# Sheet2.net
KiCad netlist of a schematic drawn in Altium Designer
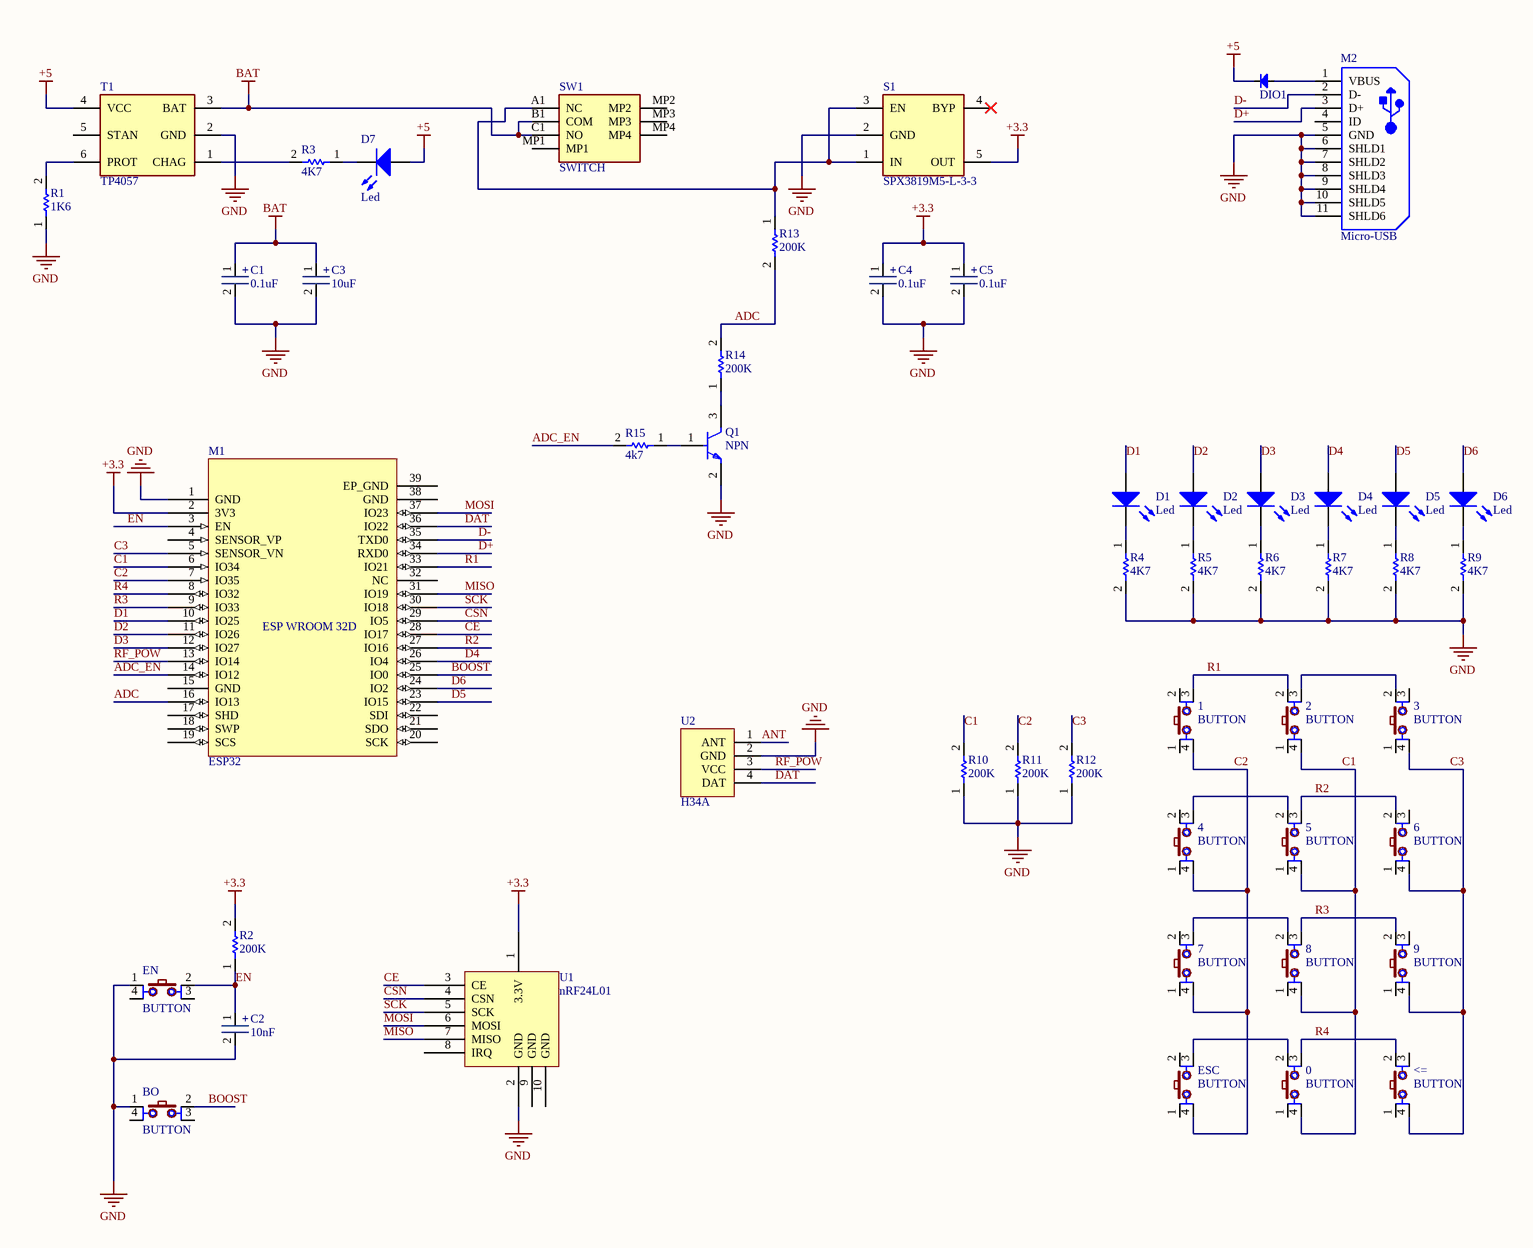
[diagram p0: Sheet2.SchDoc]

(export (version "E")
  (design (tool "Eeschema 10.0.6"))
  (components
    (comp (ref "0")
      (value "BUTTON")
      (footprint "BUTTON 4X4mm")
      (libsource (lib "Librarys") (part "BUTTON 4 PIN"))
    )
    (comp (ref "1")
      (value "BUTTON")
      (footprint "BUTTON 4X4mm")
      (libsource (lib "Librarys") (part "BUTTON 4 PIN"))
    )
    (comp (ref "2")
      (value "BUTTON")
      (footprint "BUTTON 4X4mm")
      (libsource (lib "Librarys") (part "BUTTON 4 PIN"))
    )
    (comp (ref "3")
      (value "BUTTON")
      (footprint "BUTTON 4X4mm")
      (libsource (lib "Librarys") (part "BUTTON 4 PIN"))
    )
    (comp (ref "4")
      (value "BUTTON")
      (footprint "BUTTON 4X4mm")
      (libsource (lib "Librarys") (part "BUTTON 4 PIN"))
    )
    (comp (ref "5")
      (value "BUTTON")
      (footprint "BUTTON 4X4mm")
      (libsource (lib "Librarys") (part "BUTTON 4 PIN"))
    )
    (comp (ref "6")
      (value "BUTTON")
      (footprint "BUTTON 4X4mm")
      (libsource (lib "Librarys") (part "BUTTON 4 PIN"))
    )
    (comp (ref "7")
      (value "BUTTON")
      (footprint "BUTTON 4X4mm")
      (libsource (lib "Librarys") (part "BUTTON 4 PIN"))
    )
    (comp (ref "8")
      (value "BUTTON")
      (footprint "BUTTON 4X4mm")
      (libsource (lib "Librarys") (part "BUTTON 4 PIN"))
    )
    (comp (ref "9")
      (value "BUTTON")
      (footprint "BUTTON 4X4mm")
      (libsource (lib "Librarys") (part "BUTTON 4 PIN"))
    )
    (comp (ref "<=")
      (value "BUTTON")
      (footprint "BUTTON 4X4mm")
      (libsource (lib "Librarys") (part "BUTTON 4 PIN"))
    )
    (comp (ref "BO")
      (value "BUTTON")
      (footprint "BUTTON 3x4mm 4PIN")
      (libsource (lib "Librarys") (part "BUTTON 4 PIN"))
    )
    (comp (ref "C1")
      (value "0.1uF")
      (footprint "Cap_0603_A")
      (description "General Purpose Ceramic Capacitor, 0603, 1nF, 10%, X7R, 15%, 50V")
      (fields (field (name "VOLTAGE") "50V") (field (name "TOLERANCE") "10%"))
      (libsource (lib "ResCapTransDio") (part "Capacitor"))
    )
    (comp (ref "C2")
      (value "10nF")
      (footprint "Cap_0603_A")
      (description "General Purpose Ceramic Capacitor, 0603, 1nF, 10%, X7R, 15%, 50V")
      (fields (field (name "VOLTAGE") "50V") (field (name "TOLERANCE") "10%"))
      (libsource (lib "ResCapTransDio") (part "Capacitor"))
    )
    (comp (ref "C3")
      (value "10uF")
      (footprint "Cap_0603_A")
      (description "General Purpose Ceramic Capacitor, 0603, 1nF, 10%, X7R, 15%, 50V")
      (fields (field (name "VOLTAGE") "50V") (field (name "TOLERANCE") "10%"))
      (libsource (lib "ResCapTransDio") (part "Capacitor"))
    )
    (comp (ref "C4")
      (value "0.1uF")
      (footprint "Cap_0603_A")
      (description "General Purpose Ceramic Capacitor, 0603, 1nF, 10%, X7R, 15%, 50V")
      (fields (field (name "VOLTAGE") "50V") (field (name "TOLERANCE") "10%"))
      (libsource (lib "ResCapTransDio") (part "Capacitor"))
    )
    (comp (ref "C5")
      (value "0.1uF")
      (footprint "Cap_0603_A")
      (description "General Purpose Ceramic Capacitor, 0603, 1nF, 10%, X7R, 15%, 50V")
      (fields (field (name "VOLTAGE") "50V") (field (name "TOLERANCE") "10%"))
      (libsource (lib "ResCapTransDio") (part "Capacitor"))
    )
    (comp (ref "D1") (value "Led") (footprint "LED 0603") (libsource (lib "ResCapTransDio") (part "Led")))
    (comp (ref "D2") (value "Led") (footprint "LED 0603") (libsource (lib "ResCapTransDio") (part "Led")))
    (comp (ref "D3") (value "Led") (footprint "LED 0603") (libsource (lib "ResCapTransDio") (part "Led")))
    (comp (ref "D4") (value "Led") (footprint "LED 0603") (libsource (lib "ResCapTransDio") (part "Led")))
    (comp (ref "D5") (value "Led") (footprint "LED 0603") (libsource (lib "ResCapTransDio") (part "Led")))
    (comp (ref "D6") (value "Led") (footprint "LED 0603") (libsource (lib "ResCapTransDio") (part "Led")))
    (comp (ref "D7") (value "Led") (footprint "LED 0603") (libsource (lib "ResCapTransDio") (part "Led")))
    (comp (ref "DIO1")
      (value "Diode SMD")
      (footprint "DIO-SMD-123")
      (description "Default Diode")
      (fields (field (name "PUBLISHER") "Altium Limited"))
      (libsource (lib "TechMT.VN_Lib_Project v2") (part "Diode SMD"))
    )
    (comp (ref "EN")
      (value "BUTTON")
      (footprint "BUTTON 3x4mm 4PIN")
      (libsource (lib "Librarys") (part "BUTTON 4 PIN"))
    )
    (comp (ref "ESC")
      (value "BUTTON")
      (footprint "BUTTON 4X4mm")
      (libsource (lib "Librarys") (part "BUTTON 4 PIN"))
    )
    (comp (ref "M1")
      (value "ESP32")
      (footprint "ESP32-WROOM-32D")
      (libsource (lib "ESP-WROOM-32D") (part "ESP32"))
    )
    (comp (ref "M2")
      (value "Micro-USB")
      (footprint "2.0 5 PIN SMD")
      (libsource (lib "Librarys") (part "Micro-USB"))
    )
    (comp (ref "Q1")
      (value "NPN")
      (footprint "FP-SOT23-IPC_C")
      (libsource (lib "ResCapTransDio") (part "NPN"))
    )
    (comp (ref "R1")
      (value "1K6")
      (footprint "Res_0603")
      (libsource (lib "ResCapTransDio") (part "Resistor"))
    )
    (comp (ref "R2")
      (value "200K")
      (footprint "Res_0603")
      (libsource (lib "ResCapTransDio") (part "Resistor"))
    )
    (comp (ref "R3")
      (value "4K7")
      (footprint "Res_0603")
      (libsource (lib "ResCapTransDio") (part "Resistor"))
    )
    (comp (ref "R4")
      (value "4K7")
      (footprint "Res_0603")
      (libsource (lib "ResCapTransDio") (part "Resistor"))
    )
    (comp (ref "R5")
      (value "4K7")
      (footprint "Res_0603")
      (libsource (lib "ResCapTransDio") (part "Resistor"))
    )
    (comp (ref "R6")
      (value "4K7")
      (footprint "Res_0603")
      (libsource (lib "ResCapTransDio") (part "Resistor"))
    )
    (comp (ref "R7")
      (value "4K7")
      (footprint "Res_0603")
      (libsource (lib "ResCapTransDio") (part "Resistor"))
    )
    (comp (ref "R8")
      (value "4K7")
      (footprint "Res_0603")
      (libsource (lib "ResCapTransDio") (part "Resistor"))
    )
    (comp (ref "R9")
      (value "4K7")
      (footprint "Res_0603")
      (libsource (lib "ResCapTransDio") (part "Resistor"))
    )
    (comp (ref "R10")
      (value "200K")
      (footprint "Res_0603")
      (libsource (lib "ResCapTransDio") (part "Resistor"))
    )
    (comp (ref "R11")
      (value "200K")
      (footprint "Res_0603")
      (libsource (lib "ResCapTransDio") (part "Resistor"))
    )
    (comp (ref "R12")
      (value "200K")
      (footprint "Res_0603")
      (libsource (lib "ResCapTransDio") (part "Resistor"))
    )
    (comp (ref "R13")
      (value "200K")
      (footprint "Res_0603")
      (libsource (lib "ResCapTransDio") (part "Resistor"))
    )
    (comp (ref "R14")
      (value "200K")
      (footprint "Res_0603")
      (libsource (lib "ResCapTransDio") (part "Resistor"))
    )
    (comp (ref "R15")
      (value "4k7")
      (footprint "Res_0603")
      (libsource (lib "ResCapTransDio") (part "Resistor"))
    )
    (comp (ref "S1")
      (value "SPX3819M5-L-3-3")
      (footprint "FP-C04-091-OT-IPC_A")
      (description "Regulator 250mA")
      (libsource (lib "Regulator") (part "SPX3819M5-L-3-3"))
    )
    (comp (ref "SW1") (value "SWITCH") (footprint "MSK12C02") (libsource (lib "Librarys") (part "SWITCH")))
    (comp (ref "T1") (value "TP4057") (footprint "TP4057") (libsource (lib "Librarys") (part "TP4057")))
    (comp (ref "U1")
      (value "nRF24L01")
      (footprint "NRF24L01 + PA SMD")
      (libsource (lib "MODULEs") (part "nRF24L01"))
    )
    (comp (ref "U2") (value "H34A") (footprint "H34A") (libsource (lib "MODULEs") (part "H34A")))
  )
  (nets
    (net (code "1") (name "+3.3") (class "Default")
      (node (ref "C4") (pin "1") (pinfunction "1_1") (pintype "passive"))
      (node (ref "C5") (pin "1") (pinfunction "1_1") (pintype "passive"))
      (node (ref "M1") (pin "2") (pinfunction "3V3_2") (pintype "passive"))
      (node (ref "R2") (pin "2") (pinfunction "2_2") (pintype "passive"))
      (node (ref "S1") (pin "5") (pinfunction "OUT_5") (pintype "passive"))
      (node (ref "U1") (pin "1") (pinfunction "3.3V_1") (pintype "passive"))
    )
    (net (code "2") (name "+5") (class "Default")
      (node (ref "D7") (pin "1") (pinfunction "A_1") (pintype "passive"))
      (node (ref "DIO1") (pin "2") (pinfunction "K_2") (pintype "passive"))
      (node (ref "T1") (pin "4") (pinfunction "VCC_4") (pintype "power_in"))
    )
    (net (code "3") (name "/ADC") (class "Default")
      (node (ref "M1") (pin "16") (pinfunction "IO13_16") (pintype "bidirectional"))
      (node (ref "R13") (pin "2") (pinfunction "2_2") (pintype "passive"))
      (node (ref "R14") (pin "2") (pinfunction "2_2") (pintype "passive"))
    )
    (net (code "4") (name "/ADC_EN") (class "Default")
      (node (ref "M1") (pin "14") (pinfunction "IO12_14") (pintype "bidirectional"))
      (node (ref "R15") (pin "2") (pinfunction "2_2") (pintype "passive"))
    )
    (net (code "5") (name "/ANT") (class "Default")
      (node (ref "U2") (pin "1") (pinfunction "ANT_1") (pintype "passive"))
    )
    (net (code "6") (name "/BOOST") (class "Default")
      (node (ref "BO") (pin "2") (pinfunction "2_2") (pintype "passive"))
      (node (ref "M1") (pin "25") (pinfunction "IO0_25") (pintype "bidirectional"))
    )
    (net (code "7") (name "/C1") (class "Default")
      (node (ref "0") (pin "4") (pinfunction "4_4") (pintype "passive"))
      (node (ref "2") (pin "4") (pinfunction "4_4") (pintype "passive"))
      (node (ref "5") (pin "4") (pinfunction "4_4") (pintype "passive"))
      (node (ref "8") (pin "4") (pinfunction "4_4") (pintype "passive"))
      (node (ref "M1") (pin "6") (pinfunction "IO34_6") (pintype "input"))
      (node (ref "R10") (pin "2") (pinfunction "2_2") (pintype "passive"))
    )
    (net (code "8") (name "/C2") (class "Default")
      (node (ref "1") (pin "4") (pinfunction "4_4") (pintype "passive"))
      (node (ref "4") (pin "4") (pinfunction "4_4") (pintype "passive"))
      (node (ref "7") (pin "4") (pinfunction "4_4") (pintype "passive"))
      (node (ref "ESC") (pin "4") (pinfunction "4_4") (pintype "passive"))
      (node (ref "M1") (pin "7") (pinfunction "IO35_7") (pintype "input"))
      (node (ref "R11") (pin "2") (pinfunction "2_2") (pintype "passive"))
    )
    (net (code "9") (name "/C3") (class "Default")
      (node (ref "3") (pin "4") (pinfunction "4_4") (pintype "passive"))
      (node (ref "6") (pin "4") (pinfunction "4_4") (pintype "passive"))
      (node (ref "9") (pin "4") (pinfunction "4_4") (pintype "passive"))
      (node (ref "<=") (pin "4") (pinfunction "4_4") (pintype "passive"))
      (node (ref "M1") (pin "5") (pinfunction "SENSOR_VN_5") (pintype "input"))
      (node (ref "R12") (pin "2") (pinfunction "2_2") (pintype "passive"))
    )
    (net (code "10") (name "/CE") (class "Default")
      (node (ref "M1") (pin "28") (pinfunction "IO17_28") (pintype "bidirectional"))
      (node (ref "U1") (pin "3") (pinfunction "CE_3") (pintype "passive"))
    )
    (net (code "11") (name "/CSN") (class "Default")
      (node (ref "M1") (pin "29") (pinfunction "IO5_29") (pintype "bidirectional"))
      (node (ref "U1") (pin "4") (pinfunction "CSN_4") (pintype "passive"))
    )
    (net (code "12") (name "/D+") (class "Default")
      (node (ref "M1") (pin "34") (pinfunction "RXD0_34") (pintype "bidirectional"))
      (node (ref "M2") (pin "3") (pinfunction "D+_3") (pintype "passive"))
    )
    (net (code "13") (name "/D-") (class "Default")
      (node (ref "M1") (pin "35") (pinfunction "TXD0_35") (pintype "bidirectional"))
      (node (ref "M2") (pin "2") (pinfunction "D-_2") (pintype "passive"))
    )
    (net (code "14") (name "/D1") (class "Default")
      (node (ref "D1") (pin "1") (pinfunction "A_1") (pintype "passive"))
      (node (ref "M1") (pin "10") (pinfunction "IO25_10") (pintype "bidirectional"))
    )
    (net (code "15") (name "/D2") (class "Default")
      (node (ref "D2") (pin "1") (pinfunction "A_1") (pintype "passive"))
      (node (ref "M1") (pin "11") (pinfunction "IO26_11") (pintype "bidirectional"))
    )
    (net (code "16") (name "/D3") (class "Default")
      (node (ref "D3") (pin "1") (pinfunction "A_1") (pintype "passive"))
      (node (ref "M1") (pin "12") (pinfunction "IO27_12") (pintype "bidirectional"))
    )
    (net (code "17") (name "/D4") (class "Default")
      (node (ref "D4") (pin "1") (pinfunction "A_1") (pintype "passive"))
      (node (ref "M1") (pin "26") (pinfunction "IO4_26") (pintype "bidirectional"))
    )
    (net (code "18") (name "/D5") (class "Default")
      (node (ref "D5") (pin "1") (pinfunction "A_1") (pintype "passive"))
      (node (ref "M1") (pin "23") (pinfunction "IO15_23") (pintype "bidirectional"))
    )
    (net (code "19") (name "/D6") (class "Default")
      (node (ref "D6") (pin "1") (pinfunction "A_1") (pintype "passive"))
      (node (ref "M1") (pin "24") (pinfunction "IO2_24") (pintype "bidirectional"))
    )
    (net (code "20") (name "/DAT") (class "Default")
      (node (ref "M1") (pin "36") (pinfunction "IO22_36") (pintype "bidirectional"))
      (node (ref "U2") (pin "4") (pinfunction "DAT_4") (pintype "passive"))
    )
    (net (code "21") (name "/EN") (class "Default")
      (node (ref "C2") (pin "1") (pinfunction "1_1") (pintype "passive"))
      (node (ref "EN") (pin "2") (pinfunction "2_2") (pintype "passive"))
      (node (ref "M1") (pin "3") (pinfunction "EN_3") (pintype "input"))
      (node (ref "R2") (pin "1") (pinfunction "1_1") (pintype "passive"))
    )
    (net (code "22") (name "/MISO") (class "Default")
      (node (ref "M1") (pin "31") (pinfunction "IO19_31") (pintype "bidirectional"))
      (node (ref "U1") (pin "7") (pinfunction "MISO_7") (pintype "passive"))
    )
    (net (code "23") (name "/MOSI") (class "Default")
      (node (ref "M1") (pin "37") (pinfunction "IO23_37") (pintype "bidirectional"))
      (node (ref "U1") (pin "6") (pinfunction "MOSI_6") (pintype "passive"))
    )
    (net (code "24") (name "/R1") (class "Default")
      (node (ref "1") (pin "3") (pinfunction "3_3") (pintype "passive"))
      (node (ref "2") (pin "2") (pinfunction "2_2") (pintype "passive"))
      (node (ref "M1") (pin "33") (pinfunction "IO21_33") (pintype "bidirectional"))
    )
    (net (code "25") (name "/R2") (class "Default")
      (node (ref "5") (pin "3") (pinfunction "3_3") (pintype "passive"))
      (node (ref "6") (pin "2") (pinfunction "2_2") (pintype "passive"))
      (node (ref "M1") (pin "27") (pinfunction "IO16_27") (pintype "bidirectional"))
    )
    (net (code "26") (name "/R3") (class "Default")
      (node (ref "8") (pin "3") (pinfunction "3_3") (pintype "passive"))
      (node (ref "9") (pin "2") (pinfunction "2_2") (pintype "passive"))
      (node (ref "M1") (pin "9") (pinfunction "IO33_9") (pintype "bidirectional"))
    )
    (net (code "27") (name "/R4") (class "Default")
      (node (ref "0") (pin "3") (pinfunction "3_3") (pintype "passive"))
      (node (ref "<=") (pin "2") (pinfunction "2_2") (pintype "passive"))
      (node (ref "M1") (pin "8") (pinfunction "IO32_8") (pintype "bidirectional"))
    )
    (net (code "28") (name "/RF_POW") (class "Default")
      (node (ref "M1") (pin "13") (pinfunction "IO14_13") (pintype "bidirectional"))
      (node (ref "U2") (pin "3") (pinfunction "VCC_3") (pintype "passive"))
    )
    (net (code "29") (name "/SCK") (class "Default")
      (node (ref "M1") (pin "30") (pinfunction "IO18_30") (pintype "bidirectional"))
      (node (ref "U1") (pin "5") (pinfunction "SCK_5") (pintype "passive"))
    )
    (net (code "30") (name "BAT") (class "Default")
      (node (ref "C1") (pin "1") (pinfunction "1_1") (pintype "passive"))
      (node (ref "C3") (pin "1") (pinfunction "1_1") (pintype "passive"))
      (node (ref "SW1") (pin "B1") (pinfunction "COM_B1") (pintype "passive"))
      (node (ref "SW1") (pin "C1") (pinfunction "NO_C1") (pintype "passive"))
      (node (ref "T1") (pin "3") (pinfunction "BAT_3") (pintype "power_in"))
    )
    (net (code "31") (name "GND") (class "Default")
      (node (ref "BO") (pin "1") (pintype "passive"))
      (node (ref "C1") (pin "2") (pinfunction "2_2") (pintype "passive"))
      (node (ref "C2") (pin "2") (pinfunction "2_2") (pintype "passive"))
      (node (ref "C3") (pin "2") (pinfunction "2_2") (pintype "passive"))
      (node (ref "C4") (pin "2") (pinfunction "2_2") (pintype "passive"))
      (node (ref "C5") (pin "2") (pinfunction "2_2") (pintype "passive"))
      (node (ref "EN") (pin "1") (pintype "passive"))
      (node (ref "M1") (pin "1") (pinfunction "GND_1") (pintype "passive"))
      (node (ref "M2") (pin "10") (pinfunction "SHLD5_10") (pintype "passive"))
      (node (ref "M2") (pin "11") (pinfunction "SHLD6_11") (pintype "passive"))
      (node (ref "M2") (pin "5") (pinfunction "GND_5") (pintype "passive"))
      (node (ref "M2") (pin "6") (pinfunction "SHLD1_6") (pintype "passive"))
      (node (ref "M2") (pin "7") (pinfunction "SHLD2_7") (pintype "passive"))
      (node (ref "M2") (pin "8") (pinfunction "SHLD3_8") (pintype "passive"))
      (node (ref "M2") (pin "9") (pinfunction "SHLD4_9") (pintype "passive"))
      (node (ref "Q1") (pin "2") (pinfunction "E_2") (pintype "passive"))
      (node (ref "R1") (pin "1") (pinfunction "1_1") (pintype "passive"))
      (node (ref "R10") (pin "1") (pinfunction "1_1") (pintype "passive"))
      (node (ref "R11") (pin "1") (pinfunction "1_1") (pintype "passive"))
      (node (ref "R12") (pin "1") (pinfunction "1_1") (pintype "passive"))
      (node (ref "R4") (pin "2") (pinfunction "2_2") (pintype "passive"))
      (node (ref "R5") (pin "2") (pinfunction "2_2") (pintype "passive"))
      (node (ref "R6") (pin "2") (pinfunction "2_2") (pintype "passive"))
      (node (ref "R7") (pin "2") (pinfunction "2_2") (pintype "passive"))
      (node (ref "R8") (pin "2") (pinfunction "2_2") (pintype "passive"))
      (node (ref "R9") (pin "2") (pinfunction "2_2") (pintype "passive"))
      (node (ref "S1") (pin "2") (pinfunction "GND_2") (pintype "passive"))
      (node (ref "T1") (pin "2") (pinfunction "GND_2") (pintype "passive"))
      (node (ref "U1") (pin "2") (pinfunction "GND_2") (pintype "passive"))
      (node (ref "U2") (pin "2") (pinfunction "GND_2") (pintype "passive"))
    )
    (net (code "32") (name "Net-(0-Pad2)") (class "Default")
      (node (ref "0") (pin "2") (pinfunction "2_2") (pintype "passive"))
      (node (ref "ESC") (pin "3") (pinfunction "3_3") (pintype "passive"))
    )
    (net (code "33") (name "Net-(2-Pad3)") (class "Default")
      (node (ref "2") (pin "3") (pinfunction "3_3") (pintype "passive"))
      (node (ref "3") (pin "2") (pinfunction "2_2") (pintype "passive"))
    )
    (net (code "34") (name "Net-(4-Pad3)") (class "Default")
      (node (ref "4") (pin "3") (pinfunction "3_3") (pintype "passive"))
      (node (ref "5") (pin "2") (pinfunction "2_2") (pintype "passive"))
    )
    (net (code "35") (name "Net-(7-Pad3)") (class "Default")
      (node (ref "7") (pin "3") (pinfunction "3_3") (pintype "passive"))
      (node (ref "8") (pin "2") (pinfunction "2_2") (pintype "passive"))
    )
    (net (code "36") (name "Net-(D1-K)") (class "Default")
      (node (ref "D1") (pin "2") (pinfunction "K_2") (pintype "passive"))
      (node (ref "R4") (pin "1") (pinfunction "1_1") (pintype "passive"))
    )
    (net (code "37") (name "Net-(D2-K)") (class "Default")
      (node (ref "D2") (pin "2") (pinfunction "K_2") (pintype "passive"))
      (node (ref "R5") (pin "1") (pinfunction "1_1") (pintype "passive"))
    )
    (net (code "38") (name "Net-(D3-K)") (class "Default")
      (node (ref "D3") (pin "2") (pinfunction "K_2") (pintype "passive"))
      (node (ref "R6") (pin "1") (pinfunction "1_1") (pintype "passive"))
    )
    (net (code "39") (name "Net-(D4-K)") (class "Default")
      (node (ref "D4") (pin "2") (pinfunction "K_2") (pintype "passive"))
      (node (ref "R7") (pin "1") (pinfunction "1_1") (pintype "passive"))
    )
    (net (code "40") (name "Net-(D5-K)") (class "Default")
      (node (ref "D5") (pin "2") (pinfunction "K_2") (pintype "passive"))
      (node (ref "R8") (pin "1") (pinfunction "1_1") (pintype "passive"))
    )
    (net (code "41") (name "Net-(D6-K)") (class "Default")
      (node (ref "D6") (pin "2") (pinfunction "K_2") (pintype "passive"))
      (node (ref "R9") (pin "1") (pinfunction "1_1") (pintype "passive"))
    )
    (net (code "42") (name "Net-(D7-K)") (class "Default")
      (node (ref "D7") (pin "2") (pinfunction "K_2") (pintype "passive"))
      (node (ref "R3") (pin "1") (pinfunction "1_1") (pintype "passive"))
    )
    (net (code "43") (name "Net-(DIO1-A)") (class "Default")
      (node (ref "DIO1") (pin "1") (pinfunction "A_1") (pintype "passive"))
      (node (ref "M2") (pin "1") (pinfunction "VBUS_1") (pintype "passive"))
    )
    (net (code "44") (name "Net-(Q1-B)") (class "Default")
      (node (ref "Q1") (pin "1") (pinfunction "B_1") (pintype "passive"))
      (node (ref "R15") (pin "1") (pinfunction "1_1") (pintype "passive"))
    )
    (net (code "45") (name "Net-(Q1-C)") (class "Default")
      (node (ref "Q1") (pin "3") (pinfunction "C_3") (pintype "passive"))
      (node (ref "R14") (pin "1") (pinfunction "1_1") (pintype "passive"))
    )
    (net (code "46") (name "Net-(S1-EN)") (class "Default")
      (node (ref "R13") (pin "1") (pinfunction "1_1") (pintype "passive"))
      (node (ref "S1") (pin "1") (pinfunction "IN_1") (pintype "power_in"))
      (node (ref "S1") (pin "3") (pinfunction "EN_3") (pintype "power_in"))
      (node (ref "SW1") (pin "A1") (pinfunction "NC_A1") (pintype "passive"))
    )
    (net (code "47") (name "Net-(T1-CHAG)") (class "Default")
      (node (ref "R3") (pin "2") (pinfunction "2_2") (pintype "passive"))
      (node (ref "T1") (pin "1") (pinfunction "CHAG_1") (pintype "power_in"))
    )
    (net (code "48") (name "Net-(T1-PROT)") (class "Default")
      (node (ref "R1") (pin "2") (pinfunction "2_2") (pintype "passive"))
      (node (ref "T1") (pin "6") (pinfunction "PROT_6") (pintype "passive"))
    )
    (net (code "49") (name "unconnected-(0-Pad1)") (class "Default")
      (node (ref "0") (pin "1") (pintype "passive"))
    )
    (net (code "50") (name "unconnected-(1-Pad1)") (class "Default")
      (node (ref "1") (pin "1") (pintype "passive"))
    )
    (net (code "51") (name "unconnected-(1-Pad2)") (class "Default")
      (node (ref "1") (pin "2") (pinfunction "2_2") (pintype "passive"))
    )
    (net (code "52") (name "unconnected-(2-Pad1)") (class "Default")
      (node (ref "2") (pin "1") (pintype "passive"))
    )
    (net (code "53") (name "unconnected-(3-Pad1)") (class "Default")
      (node (ref "3") (pin "1") (pintype "passive"))
    )
    (net (code "54") (name "unconnected-(3-Pad3)") (class "Default")
      (node (ref "3") (pin "3") (pinfunction "3_3") (pintype "passive"))
    )
    (net (code "55") (name "unconnected-(4-Pad1)") (class "Default")
      (node (ref "4") (pin "1") (pintype "passive"))
    )
    (net (code "56") (name "unconnected-(4-Pad2)") (class "Default")
      (node (ref "4") (pin "2") (pinfunction "2_2") (pintype "passive"))
    )
    (net (code "57") (name "unconnected-(5-Pad1)") (class "Default")
      (node (ref "5") (pin "1") (pintype "passive"))
    )
    (net (code "58") (name "unconnected-(6-Pad1)") (class "Default")
      (node (ref "6") (pin "1") (pintype "passive"))
    )
    (net (code "59") (name "unconnected-(6-Pad3)") (class "Default")
      (node (ref "6") (pin "3") (pinfunction "3_3") (pintype "passive"))
    )
    (net (code "60") (name "unconnected-(7-Pad1)") (class "Default")
      (node (ref "7") (pin "1") (pintype "passive"))
    )
    (net (code "61") (name "unconnected-(7-Pad2)") (class "Default")
      (node (ref "7") (pin "2") (pinfunction "2_2") (pintype "passive"))
    )
    (net (code "62") (name "unconnected-(8-Pad1)") (class "Default")
      (node (ref "8") (pin "1") (pintype "passive"))
    )
    (net (code "63") (name "unconnected-(9-Pad1)") (class "Default")
      (node (ref "9") (pin "1") (pintype "passive"))
    )
    (net (code "64") (name "unconnected-(9-Pad3)") (class "Default")
      (node (ref "9") (pin "3") (pinfunction "3_3") (pintype "passive"))
    )
    (net (code "65") (name "unconnected-(<=-Pad1)") (class "Default")
      (node (ref "<=") (pin "1") (pintype "passive"))
    )
    (net (code "66") (name "unconnected-(<=-Pad3)") (class "Default")
      (node (ref "<=") (pin "3") (pinfunction "3_3") (pintype "passive"))
    )
    (net (code "67") (name "unconnected-(BO-Pad3)") (class "Default")
      (node (ref "BO") (pin "3") (pinfunction "3_3") (pintype "passive"))
    )
    (net (code "68") (name "unconnected-(BO-Pad4)") (class "Default")
      (node (ref "BO") (pin "4") (pinfunction "4_4") (pintype "passive"))
    )
    (net (code "69") (name "unconnected-(EN-Pad3)") (class "Default")
      (node (ref "EN") (pin "3") (pinfunction "3_3") (pintype "passive"))
    )
    (net (code "70") (name "unconnected-(EN-Pad4)") (class "Default")
      (node (ref "EN") (pin "4") (pinfunction "4_4") (pintype "passive"))
    )
    (net (code "71") (name "unconnected-(ESC-Pad1)") (class "Default")
      (node (ref "ESC") (pin "1") (pintype "passive"))
    )
    (net (code "72") (name "unconnected-(ESC-Pad2)") (class "Default")
      (node (ref "ESC") (pin "2") (pinfunction "2_2") (pintype "passive"))
    )
    (net (code "73") (name "unconnected-(M1-EP_GND-Pad39)") (class "Default")
      (node (ref "M1") (pin "39") (pinfunction "EP_GND_39") (pintype "passive"))
    )
    (net (code "74") (name "unconnected-(M1-GND-Pad15)") (class "Default")
      (node (ref "M1") (pin "15") (pinfunction "GND_15") (pintype "passive"))
    )
    (net (code "75") (name "unconnected-(M1-GND-Pad38)") (class "Default")
      (node (ref "M1") (pin "38") (pinfunction "GND_38") (pintype "passive"))
    )
    (net (code "76") (name "unconnected-(M1-NC-Pad32)") (class "Default")
      (node (ref "M1") (pin "32") (pinfunction "NC_32") (pintype "passive"))
    )
    (net (code "77") (name "unconnected-(M1-SCK-Pad20)") (class "Default")
      (node (ref "M1") (pin "20") (pinfunction "SCK_20") (pintype "bidirectional"))
    )
    (net (code "78") (name "unconnected-(M1-SCS-Pad19)") (class "Default")
      (node (ref "M1") (pin "19") (pinfunction "SCS_19") (pintype "bidirectional"))
    )
    (net (code "79") (name "unconnected-(M1-SDI-Pad22)") (class "Default")
      (node (ref "M1") (pin "22") (pinfunction "SDI_22") (pintype "bidirectional"))
    )
    (net (code "80") (name "unconnected-(M1-SDO-Pad21)") (class "Default")
      (node (ref "M1") (pin "21") (pinfunction "SDO_21") (pintype "bidirectional"))
    )
    (net (code "81") (name "unconnected-(M1-SENSOR_VP-Pad4)") (class "Default")
      (node (ref "M1") (pin "4") (pinfunction "SENSOR_VP_4") (pintype "input"))
    )
    (net (code "82") (name "unconnected-(M1-SHD-Pad17)") (class "Default")
      (node (ref "M1") (pin "17") (pinfunction "SHD_17") (pintype "bidirectional"))
    )
    (net (code "83") (name "unconnected-(M1-SWP-Pad18)") (class "Default")
      (node (ref "M1") (pin "18") (pinfunction "SWP_18") (pintype "bidirectional"))
    )
    (net (code "84") (name "unconnected-(M2-ID-Pad4)") (class "Default")
      (node (ref "M2") (pin "4") (pinfunction "ID_4") (pintype "passive"))
    )
    (net (code "85") (name "unconnected-(S1-BYP-Pad4)") (class "Default")
      (node (ref "S1") (pin "4") (pinfunction "BYP_4") (pintype "power_in+no_connect"))
    )
    (net (code "86") (name "unconnected-(SW1-PadMP1)") (class "Default")
      (node (ref "SW1") (pin "MP1") (pinfunction "MP1_MP1") (pintype "passive"))
    )
    (net (code "87") (name "unconnected-(SW1-PadMP2)") (class "Default")
      (node (ref "SW1") (pin "MP2") (pinfunction "MP2_MP2") (pintype "passive"))
    )
    (net (code "88") (name "unconnected-(SW1-PadMP3)") (class "Default")
      (node (ref "SW1") (pin "MP3") (pinfunction "MP3_MP3") (pintype "passive"))
    )
    (net (code "89") (name "unconnected-(SW1-PadMP4)") (class "Default")
      (node (ref "SW1") (pin "MP4") (pinfunction "MP4_MP4") (pintype "passive"))
    )
    (net (code "90") (name "unconnected-(T1-STAN-Pad5)") (class "Default")
      (node (ref "T1") (pin "5") (pinfunction "STAN_5") (pintype "passive"))
    )
    (net (code "91") (name "unconnected-(U1-GND-Pad9)") (class "Default")
      (node (ref "U1") (pin "9") (pinfunction "GND_9") (pintype "passive"))
    )
    (net (code "92") (name "unconnected-(U1-GND-Pad10)") (class "Default")
      (node (ref "U1") (pin "10") (pinfunction "GND_10") (pintype "passive"))
    )
    (net (code "93") (name "unconnected-(U1-IRQ-Pad8)") (class "Default")
      (node (ref "U1") (pin "8") (pinfunction "IRQ_8") (pintype "passive"))
    )
  )
)
